# MICROCONTROLLER.net
KiCad netlist of a schematic drawn in Altium Designer
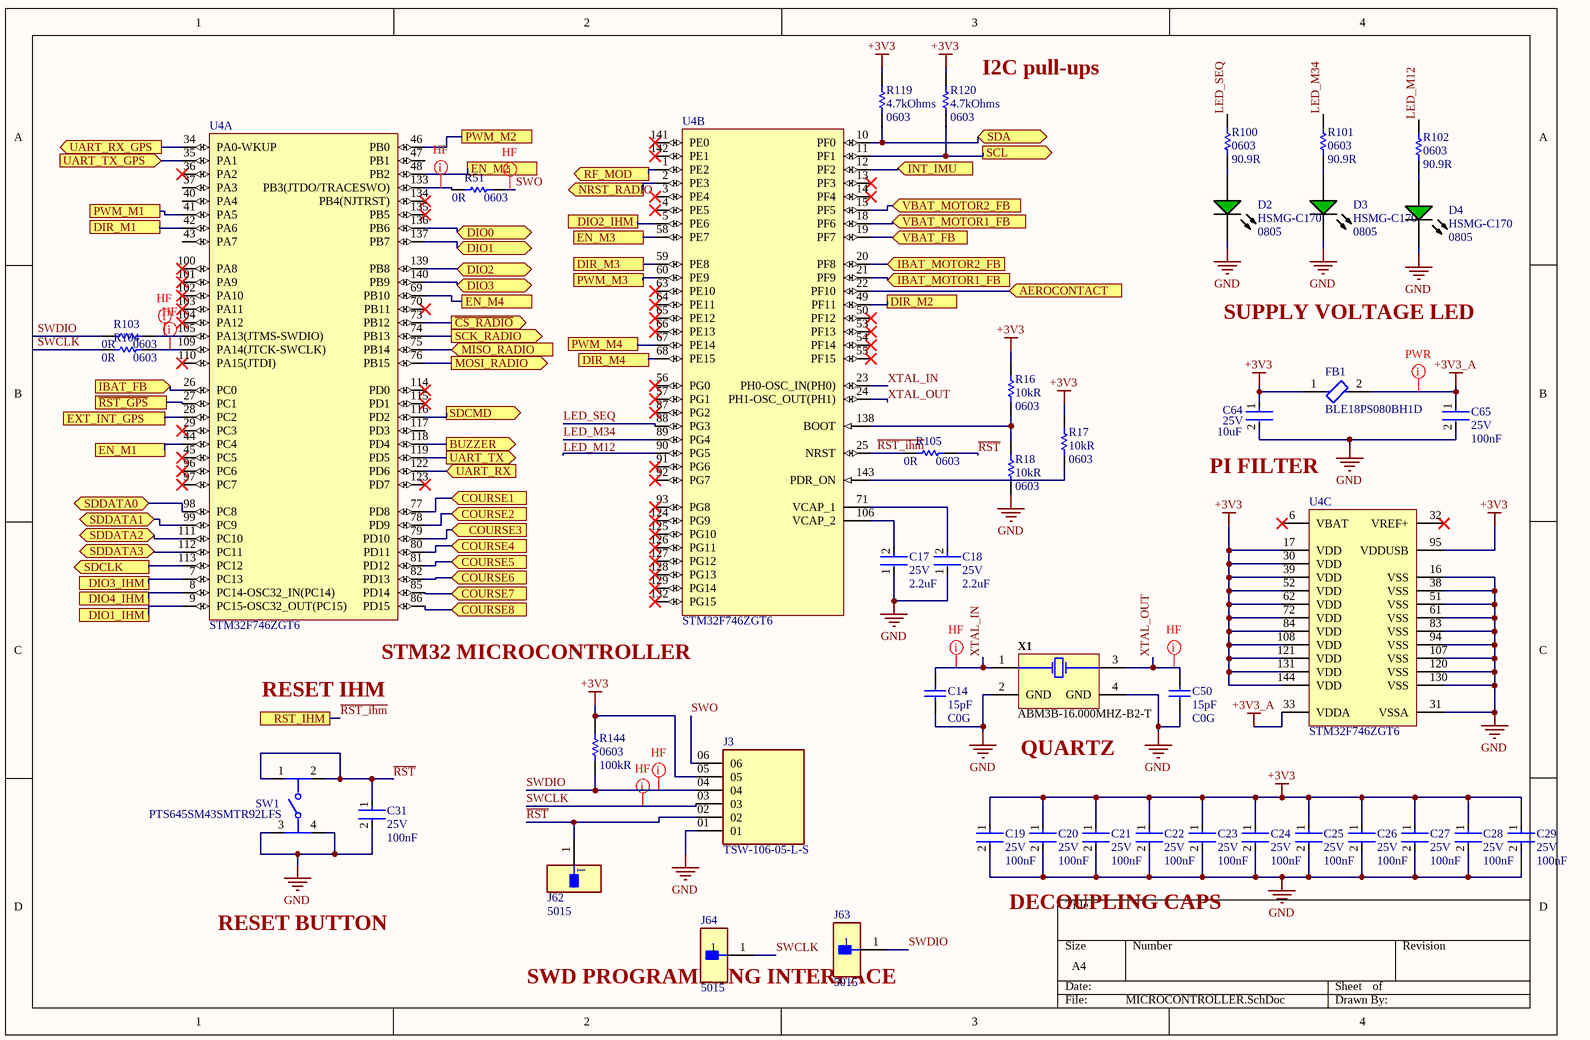
[diagram p0: MICROCONTROLLER.SchDoc]

(export (version "E")
  (design (tool "Eeschema 10.0.6"))
  (components
    (comp (ref "C14")
      (value "VJ0603D150JXPAJ")
      (footprint "CAPC1608X92X38ML15T08")
      (fields
        (field (name "MANUFACTURER") "Vitramon")
        (field (name "TOLERANCE") "5%")
        (field (name "CAPACITANCE") "15pF")
        (field (name "DIELECTRIC") "C0G")
        (field (name "VOLTAGE") "250V")
      )
      (libsource (lib "Altium Content Vault") (part "CAP"))
    )
    (comp (ref "C17")
      (value "C1608X5R1E225K080AB")
      (footprint "FP-C1608-080-0_1-MFG")
      (description "Multilayer Ceramic Capacitors 2.2μF ±10% 25V X5R SMD 0603")
      (fields
        (field (name "VOLTAGE RATING (DC)") "25V")
        (field (name "CAPACITANCE") "2.2uF")
        (field (name "TOLERANCE") "10%")
        (field (name "MANUFACTURER") "TDK")
      )
      (libsource (lib "Altium Content Vault") (part "236180d848d6139a670b325ea6854c9"))
    )
    (comp (ref "C18")
      (value "C1608X5R1E225K080AB")
      (footprint "FP-C1608-080-0_1-MFG")
      (description "Multilayer Ceramic Capacitors 2.2μF ±10% 25V X5R SMD 0603")
      (fields
        (field (name "VOLTAGE RATING (DC)") "25V")
        (field (name "CAPACITANCE") "2.2uF")
        (field (name "TOLERANCE") "10%")
        (field (name "MANUFACTURER") "TDK")
      )
      (libsource (lib "Altium Content Vault") (part "236180d848d6139a670b325ea6854c9"))
    )
    (comp (ref "C19")
      (value "CGA3E2X7R1E104K080AA")
      (footprint "FP-CGA3E-0_3-0_1-MFG")
      (description "Cap Ceramic 100nF 25V X7R 10% Pad SMD 0603 +125°C Automotive T/R")
      (fields
        (field (name "VOLTAGE RATING (DC)") "25V")
        (field (name "CAPACITANCE") "100nF")
        (field (name "TOLERANCE") "10%")
        (field (name "MANUFACTURER") "TDK")
      )
      (libsource (lib "Altium Content Vault") (part "b4654b650e69147ec39a6b967a45e02"))
    )
    (comp (ref "C20")
      (value "CGA3E2X7R1E104K080AA")
      (footprint "FP-CGA3E-0_3-0_1-MFG")
      (description "Cap Ceramic 100nF 25V X7R 10% Pad SMD 0603 +125°C Automotive T/R")
      (fields
        (field (name "VOLTAGE RATING (DC)") "25V")
        (field (name "CAPACITANCE") "100nF")
        (field (name "TOLERANCE") "10%")
        (field (name "MANUFACTURER") "TDK")
      )
      (libsource (lib "Altium Content Vault") (part "b4654b650e69147ec39a6b967a45e02"))
    )
    (comp (ref "C21")
      (value "CGA3E2X7R1E104K080AA")
      (footprint "FP-CGA3E-0_3-0_1-MFG")
      (description "Cap Ceramic 100nF 25V X7R 10% Pad SMD 0603 +125°C Automotive T/R")
      (fields
        (field (name "VOLTAGE RATING (DC)") "25V")
        (field (name "CAPACITANCE") "100nF")
        (field (name "TOLERANCE") "10%")
        (field (name "MANUFACTURER") "TDK")
      )
      (libsource (lib "Altium Content Vault") (part "b4654b650e69147ec39a6b967a45e02"))
    )
    (comp (ref "C22")
      (value "CGA3E2X7R1E104K080AA")
      (footprint "FP-CGA3E-0_3-0_1-MFG")
      (description "Cap Ceramic 100nF 25V X7R 10% Pad SMD 0603 +125°C Automotive T/R")
      (fields
        (field (name "VOLTAGE RATING (DC)") "25V")
        (field (name "CAPACITANCE") "100nF")
        (field (name "TOLERANCE") "10%")
        (field (name "MANUFACTURER") "TDK")
      )
      (libsource (lib "Altium Content Vault") (part "b4654b650e69147ec39a6b967a45e02"))
    )
    (comp (ref "C23")
      (value "CGA3E2X7R1E104K080AA")
      (footprint "FP-CGA3E-0_3-0_1-MFG")
      (description "Cap Ceramic 100nF 25V X7R 10% Pad SMD 0603 +125°C Automotive T/R")
      (fields
        (field (name "VOLTAGE RATING (DC)") "25V")
        (field (name "CAPACITANCE") "100nF")
        (field (name "TOLERANCE") "10%")
        (field (name "MANUFACTURER") "TDK")
      )
      (libsource (lib "Altium Content Vault") (part "b4654b650e69147ec39a6b967a45e02"))
    )
    (comp (ref "C24")
      (value "CGA3E2X7R1E104K080AA")
      (footprint "FP-CGA3E-0_3-0_1-MFG")
      (description "Cap Ceramic 100nF 25V X7R 10% Pad SMD 0603 +125°C Automotive T/R")
      (fields
        (field (name "VOLTAGE RATING (DC)") "25V")
        (field (name "CAPACITANCE") "100nF")
        (field (name "TOLERANCE") "10%")
        (field (name "MANUFACTURER") "TDK")
      )
      (libsource (lib "Altium Content Vault") (part "b4654b650e69147ec39a6b967a45e02"))
    )
    (comp (ref "C25")
      (value "CGA3E2X7R1E104K080AA")
      (footprint "FP-CGA3E-0_3-0_1-MFG")
      (description "Cap Ceramic 100nF 25V X7R 10% Pad SMD 0603 +125°C Automotive T/R")
      (fields
        (field (name "VOLTAGE RATING (DC)") "25V")
        (field (name "CAPACITANCE") "100nF")
        (field (name "TOLERANCE") "10%")
        (field (name "MANUFACTURER") "TDK")
      )
      (libsource (lib "Altium Content Vault") (part "b4654b650e69147ec39a6b967a45e02"))
    )
    (comp (ref "C26")
      (value "CGA3E2X7R1E104K080AA")
      (footprint "FP-CGA3E-0_3-0_1-MFG")
      (description "Cap Ceramic 100nF 25V X7R 10% Pad SMD 0603 +125°C Automotive T/R")
      (fields
        (field (name "VOLTAGE RATING (DC)") "25V")
        (field (name "CAPACITANCE") "100nF")
        (field (name "TOLERANCE") "10%")
        (field (name "MANUFACTURER") "TDK")
      )
      (libsource (lib "Altium Content Vault") (part "b4654b650e69147ec39a6b967a45e02"))
    )
    (comp (ref "C27")
      (value "CGA3E2X7R1E104K080AA")
      (footprint "FP-CGA3E-0_3-0_1-MFG")
      (description "Cap Ceramic 100nF 25V X7R 10% Pad SMD 0603 +125°C Automotive T/R")
      (fields
        (field (name "VOLTAGE RATING (DC)") "25V")
        (field (name "CAPACITANCE") "100nF")
        (field (name "TOLERANCE") "10%")
        (field (name "MANUFACTURER") "TDK")
      )
      (libsource (lib "Altium Content Vault") (part "b4654b650e69147ec39a6b967a45e02"))
    )
    (comp (ref "C28")
      (value "CGA3E2X7R1E104K080AA")
      (footprint "FP-CGA3E-0_3-0_1-MFG")
      (description "Cap Ceramic 100nF 25V X7R 10% Pad SMD 0603 +125°C Automotive T/R")
      (fields
        (field (name "VOLTAGE RATING (DC)") "25V")
        (field (name "CAPACITANCE") "100nF")
        (field (name "TOLERANCE") "10%")
        (field (name "MANUFACTURER") "TDK")
      )
      (libsource (lib "Altium Content Vault") (part "b4654b650e69147ec39a6b967a45e02"))
    )
    (comp (ref "C29")
      (value "CGA3E2X7R1E104K080AA")
      (footprint "FP-CGA3E-0_3-0_1-MFG")
      (description "Cap Ceramic 100nF 25V X7R 10% Pad SMD 0603 +125°C Automotive T/R")
      (fields
        (field (name "VOLTAGE RATING (DC)") "25V")
        (field (name "CAPACITANCE") "100nF")
        (field (name "TOLERANCE") "10%")
        (field (name "MANUFACTURER") "TDK")
      )
      (libsource (lib "Altium Content Vault") (part "b4654b650e69147ec39a6b967a45e02"))
    )
    (comp (ref "C31")
      (value "CGA3E2X7R1E104K080AA")
      (footprint "FP-CGA3E-0_3-0_1-MFG")
      (description "Cap Ceramic 100nF 25V X7R 10% Pad SMD 0603 +125°C Automotive T/R")
      (fields
        (field (name "VOLTAGE RATING (DC)") "25V")
        (field (name "CAPACITANCE") "100nF")
        (field (name "TOLERANCE") "10%")
        (field (name "MANUFACTURER") "TDK")
      )
      (libsource (lib "Altium Content Vault") (part "b4654b650e69147ec39a6b967a45e02"))
    )
    (comp (ref "C50")
      (value "VJ0603D150JXPAJ")
      (footprint "CAPC1608X92X38ML15T08")
      (fields
        (field (name "MANUFACTURER") "Vitramon")
        (field (name "TOLERANCE") "5%")
        (field (name "CAPACITANCE") "15pF")
        (field (name "DIELECTRIC") "C0G")
        (field (name "VOLTAGE") "250V")
      )
      (libsource (lib "Altium Content Vault") (part "CAP"))
    )
    (comp (ref "C64")
      (value "C2012X5R1E106K125AB")
      (footprint "FP-C2012-125-0_2-IPC_B")
      (description "Multilayer Ceramic Capacitors 10μF ±10% 25V X5R SMD 0805")
      (fields
        (field (name "VOLTAGE") "25V")
        (field (name "VOLTAGE RATING (DC)") "25V")
        (field (name "TOLERANCE") "10%")
        (field (name "CAPACITANCE") "10uF")
      )
      (libsource (lib "Altium Content Vault") (part "b4654b650e69147ec39a6b967a45e02"))
    )
    (comp (ref "C65")
      (value "CGA3E2X7R1E104K080AA")
      (footprint "FP-CGA3E-0_3-0_1-MFG")
      (description "Cap Ceramic 100nF 25V X7R 10% Pad SMD 0603 +125°C Automotive T/R")
      (fields
        (field (name "VOLTAGE RATING (DC)") "25V")
        (field (name "CAPACITANCE") "100nF")
        (field (name "TOLERANCE") "10%")
        (field (name "MANUFACTURER") "TDK")
      )
      (libsource (lib "Altium Content Vault") (part "b4654b650e69147ec39a6b967a45e02"))
    )
    (comp (ref "D2")
      (value "HSMG-C170")
      (footprint "AVAG-HSMX-C170_V")
      (description "Chip LED, Green, 2.2 V, -40 to 85 degC, 2-Pin SMD, Pb-Free, Tape and Reel")
      (fields (field (name "MANUFACTURER") "Avago") (field (name "CASE/PACKAGE") "0805"))
      (libsource (lib "Altium Content Vault") (part "LED_GREEN_A1K2-2"))
    )
    (comp (ref "D3")
      (value "HSMG-C170")
      (footprint "AVAG-HSMX-C170_V")
      (description "Chip LED, Green, 2.2 V, -40 to 85 degC, 2-Pin SMD, Pb-Free, Tape and Reel")
      (fields (field (name "MANUFACTURER") "Avago") (field (name "CASE/PACKAGE") "0805"))
      (libsource (lib "Altium Content Vault") (part "LED_GREEN_A1K2-2"))
    )
    (comp (ref "D4")
      (value "HSMG-C170")
      (footprint "AVAG-HSMX-C170_V")
      (description "Chip LED, Green, 2.2 V, -40 to 85 degC, 2-Pin SMD, Pb-Free, Tape and Reel")
      (fields (field (name "MANUFACTURER") "Avago") (field (name "CASE/PACKAGE") "0805"))
      (libsource (lib "Altium Content Vault") (part "LED_GREEN_A1K2-2"))
    )
    (comp (ref "FB1")
      (value "BLE18PS080BH1D")
      (footprint "FP-BLE18-0_15-t0_6-MFG")
      (description "Ferrite Chip Bead 8.5Ω ±25% 5A, DCR 0.004Ω 0603 AEC-200")
      (fields (field (name "MANUFACTURER") "Murata"))
      (libsource (lib "Altium Content Vault") (part "5f30dd21d616792df468990f7003faa"))
    )
    (comp (ref "J3")
      (value "TSW-106-05-L-S")
      (footprint "TSW-106-05-L-S:SAMTEC_TSW-106-05-L-S")
      (fields (field (name "MF") "{'manufacturer': u'Samtec'}"))
      (libsource (lib "*") (part "TSW-106-05-L-S"))
    )
    (comp (ref "J62")
      (value "5015")
      (footprint "FP-5015-MFG")
      (description "PC TEST POINT MINIATURE")
      (fields
        (field (name "MANUFACTURER") "keystone")
        (field (name "OCTOPART") "https://octopart.com/5015-keystone-3822")
      )
      (libsource (lib "Altium Content Vault") (part "dd45045ce8184df9e99e12baf3f412c"))
    )
    (comp (ref "J63")
      (value "5015")
      (footprint "FP-5015-MFG")
      (description "PC TEST POINT MINIATURE")
      (fields
        (field (name "MANUFACTURER") "keystone")
        (field (name "OCTOPART") "https://octopart.com/5015-keystone-3822")
      )
      (libsource (lib "Altium Content Vault") (part "dd45045ce8184df9e99e12baf3f412c"))
    )
    (comp (ref "J64")
      (value "5015")
      (footprint "FP-5015-MFG")
      (description "PC TEST POINT MINIATURE")
      (fields
        (field (name "MANUFACTURER") "keystone")
        (field (name "OCTOPART") "https://octopart.com/5015-keystone-3822")
      )
      (libsource (lib "Altium Content Vault") (part "dd45045ce8184df9e99e12baf3f412c"))
    )
    (comp (ref "R16")
      (value "ERJ3EKF1002V")
      (footprint "RESC1609X55X30LL15T15")
      (description "Chip Resistor, 10 KOhm, +/- 1%, 0.1 W, -55 to 155 degC, 0603 (1608 Metric), RoHS, Tape and Reel")
      (fields
        (field (name "RESISTANCE") "10kR")
        (field (name "CASE CODE (IMPERIAL)") "0603")
        (field (name "TOLERANCE") "1%")
        (field (name "MANUFACTURER") "Panasonic")
      )
      (libsource (lib "Altium Content Vault") (part "RES-2"))
    )
    (comp (ref "R17")
      (value "ERJ3EKF1002V")
      (footprint "RESC1609X55X30LL15T15")
      (description "Chip Resistor, 10 KOhm, +/- 1%, 0.1 W, -55 to 155 degC, 0603 (1608 Metric), RoHS, Tape and Reel")
      (fields
        (field (name "RESISTANCE") "10kR")
        (field (name "CASE CODE (IMPERIAL)") "0603")
        (field (name "TOLERANCE") "1%")
        (field (name "MANUFACTURER") "Panasonic")
      )
      (libsource (lib "Altium Content Vault") (part "RES-2"))
    )
    (comp (ref "R18")
      (value "ERJ3EKF1002V")
      (footprint "RESC1609X55X30LL15T15")
      (description "Chip Resistor, 10 KOhm, +/- 1%, 0.1 W, -55 to 155 degC, 0603 (1608 Metric), RoHS, Tape and Reel")
      (fields
        (field (name "RESISTANCE") "10kR")
        (field (name "CASE CODE (IMPERIAL)") "0603")
        (field (name "TOLERANCE") "1%")
        (field (name "MANUFACTURER") "Panasonic")
      )
      (libsource (lib "Altium Content Vault") (part "RES-2"))
    )
    (comp (ref "R51")
      (value "RC0603JR-070RL")
      (footprint "RESC1608X55X25ML10T15")
      (description "Chip Resistor, 0 Ohm, +/- 5%, 0.1 W, -55 to 155 degC, 0603 (1608 Metric), RoHS, Tape and Reel")
      (fields
        (field (name "TOLERANCE") "5%")
        (field (name "CASE CODE (IMPERIAL)") "0603")
        (field (name "RESISTANCE") "0R")
        (field (name "MANUFACTURER") "Yageo")
      )
      (libsource (lib "Altium Content Vault") (part "RES-2"))
    )
    (comp (ref "R100")
      (value "CRCW060390R9FKEA")
      (footprint "RESC1609X50X30NL10T20")
      (fields
        (field (name "MANUFACTURER") "Vishay Dale")
        (field (name "CASE CODE (IMPERIAL)") "0603")
        (field (name "RESISTANCE") "90.9R")
        (field (name "TOLERANCE") "1%")
      )
      (libsource (lib "Altium Content Vault") (part "RES"))
    )
    (comp (ref "R101")
      (value "CRCW060390R9FKEA")
      (footprint "RESC1609X50X30NL10T20")
      (fields
        (field (name "MANUFACTURER") "Vishay Dale")
        (field (name "CASE CODE (IMPERIAL)") "0603")
        (field (name "RESISTANCE") "90.9R")
        (field (name "TOLERANCE") "1%")
      )
      (libsource (lib "Altium Content Vault") (part "RES"))
    )
    (comp (ref "R102")
      (value "CRCW060390R9FKEA")
      (footprint "RESC1609X50X30NL10T20")
      (fields
        (field (name "MANUFACTURER") "Vishay Dale")
        (field (name "CASE CODE (IMPERIAL)") "0603")
        (field (name "RESISTANCE") "90.9R")
        (field (name "TOLERANCE") "1%")
      )
      (libsource (lib "Altium Content Vault") (part "RES"))
    )
    (comp (ref "R103")
      (value "RC0603JR-070RL")
      (footprint "RESC1608X55X25ML10T15")
      (description "Chip Resistor, 0 Ohm, +/- 5%, 0.1 W, -55 to 155 degC, 0603 (1608 Metric), RoHS, Tape and Reel")
      (fields
        (field (name "TOLERANCE") "5%")
        (field (name "CASE CODE (IMPERIAL)") "0603")
        (field (name "RESISTANCE") "0R")
        (field (name "MANUFACTURER") "Yageo")
      )
      (libsource (lib "Altium Content Vault") (part "RES-2"))
    )
    (comp (ref "R104")
      (value "RC0603JR-070RL")
      (footprint "RESC1608X55X25ML10T15")
      (description "Chip Resistor, 0 Ohm, +/- 5%, 0.1 W, -55 to 155 degC, 0603 (1608 Metric), RoHS, Tape and Reel")
      (fields
        (field (name "TOLERANCE") "5%")
        (field (name "CASE CODE (IMPERIAL)") "0603")
        (field (name "RESISTANCE") "0R")
        (field (name "MANUFACTURER") "Yageo")
      )
      (libsource (lib "Altium Content Vault") (part "RES-2"))
    )
    (comp (ref "R105")
      (value "RC0603JR-070RL")
      (footprint "RESC1608X55X25ML10T15")
      (description "Chip Resistor, 0 Ohm, +/- 5%, 0.1 W, -55 to 155 degC, 0603 (1608 Metric), RoHS, Tape and Reel")
      (fields
        (field (name "TOLERANCE") "5%")
        (field (name "CASE CODE (IMPERIAL)") "0603")
        (field (name "RESISTANCE") "0R")
        (field (name "MANUFACTURER") "Yageo")
      )
      (libsource (lib "Altium Content Vault") (part "RES-2"))
    )
    (comp (ref "R119")
      (value "RC0603FR-074K7L")
      (footprint "RESC1608X55X25LL10T15")
      (description "Chip Resistor, 4.7 KOhm, +/- 1%, 0.1 W, -55 to 155 degC, 0603 (1608 Metric), RoHS, Tape and Reel")
      (fields
        (field (name "MANUFACTURER") "Yageo")
        (field (name "RESISTANCE") "4.7kOhms")
        (field (name "CASE CODE - IN") "0603")
        (field (name "TOLERANCE") "1%")
      )
      (libsource (lib "Altium Content Vault") (part "RES-2"))
    )
    (comp (ref "R120")
      (value "RC0603FR-074K7L")
      (footprint "RESC1608X55X25LL10T15")
      (description "Chip Resistor, 4.7 KOhm, +/- 1%, 0.1 W, -55 to 155 degC, 0603 (1608 Metric), RoHS, Tape and Reel")
      (fields
        (field (name "MANUFACTURER") "Yageo")
        (field (name "RESISTANCE") "4.7kOhms")
        (field (name "CASE CODE - IN") "0603")
        (field (name "TOLERANCE") "1%")
      )
      (libsource (lib "Altium Content Vault") (part "RES-2"))
    )
    (comp (ref "R144")
      (value "ERA3AEB104V")
      (footprint "RESC1608X55X30ML20T20")
      (fields
        (field (name "MANUFACTURER") "Panasonic")
        (field (name "MANUFACTURER PART NUMBER") "ERA-3AEB104V")
        (field (name "CASE CODE (IMPERIAL)") "0603")
        (field (name "RESISTANCE") "100kR")
        (field (name "TOLERANCE") "0.1%")
      )
      (libsource (lib "Altium Content Vault") (part "RES"))
    )
    (comp (ref "SW1")
      (value "PTS645SM43SMTR92LFS")
      (footprint "FP-PTS645SM43SMTR92LFS-MFG")
      (description "SWITCH TACTILE SPST-NO 0.05A 12V")
      (libsource (lib "Altium Content Vault") (part "1adf0dd01260c80cf25a44bfd6b99ba"))
    )
    (comp (ref "U4")
      (value "STM32F746ZGT6")
      (footprint "STM-LQFP144_V")
      (fields (field (name "PARTNUMBER") "STM32F746ZG") (field (name "MANUFACTURER") "STMicroelectronics"))
      (libsource (lib "Altium Content Vault") (part "STM-STM32F74X-LQFP-144"))
    )
    (comp (ref "X1")
      (value "ABM3B-16.000MHZ-B2-T")
      (footprint "ABRA-ABM3B-4_V")
      (description "Ceramic SMD Crystal, 16 MHz, +/- 20 ppm, 50 Ohm, -20 to 70 degC, 4-Pin SMD, RoHS, Tape and Reel")
      (fields (field (name "TOLERANCE") "30%"))
      (libsource (lib "Altium Content Vault") (part "XTAL-1-3-4"))
    )
  )
  (nets
    (net (code "1") (name "+3V3") (class "Default")
      (node (ref "C19") (pin "1") (pinfunction "1_1") (pintype "passive"))
      (node (ref "C20") (pin "1") (pinfunction "1_1") (pintype "passive"))
      (node (ref "C21") (pin "1") (pinfunction "1_1") (pintype "passive"))
      (node (ref "C22") (pin "1") (pinfunction "1_1") (pintype "passive"))
      (node (ref "C23") (pin "1") (pinfunction "1_1") (pintype "passive"))
      (node (ref "C24") (pin "1") (pinfunction "1_1") (pintype "passive"))
      (node (ref "C25") (pin "1") (pinfunction "1_1") (pintype "passive"))
      (node (ref "C26") (pin "1") (pinfunction "1_1") (pintype "passive"))
      (node (ref "C27") (pin "1") (pinfunction "1_1") (pintype "passive"))
      (node (ref "C28") (pin "1") (pinfunction "1_1") (pintype "passive"))
      (node (ref "C29") (pin "1") (pinfunction "1_1") (pintype "passive"))
      (node (ref "C64") (pin "1") (pinfunction "1_1") (pintype "passive"))
      (node (ref "FB1") (pin "1") (pinfunction "1_1") (pintype "passive"))
      (node (ref "J3") (pin "05") (pinfunction "05_05") (pintype "passive"))
      (node (ref "R119") (pin "2") (pinfunction "2_2") (pintype "passive"))
      (node (ref "R120") (pin "2") (pinfunction "2_2") (pintype "passive"))
      (node (ref "R144") (pin "2") (pinfunction "2_2") (pintype "passive"))
      (node (ref "R16") (pin "2") (pinfunction "2_2") (pintype "passive"))
      (node (ref "R17") (pin "2") (pinfunction "2_2") (pintype "passive"))
      (node (ref "U4") (pin "108") (pinfunction "VDD_108") (pintype "power_in"))
      (node (ref "U4") (pin "121") (pinfunction "VDD_121") (pintype "power_in"))
      (node (ref "U4") (pin "131") (pinfunction "VDD_131") (pintype "power_in"))
      (node (ref "U4") (pin "144") (pinfunction "VDD_144") (pintype "power_in"))
      (node (ref "U4") (pin "17") (pinfunction "VDD_17") (pintype "power_in"))
      (node (ref "U4") (pin "30") (pinfunction "VDD_30") (pintype "power_in"))
      (node (ref "U4") (pin "39") (pinfunction "VDD_39") (pintype "power_in"))
      (node (ref "U4") (pin "52") (pinfunction "VDD_52") (pintype "power_in"))
      (node (ref "U4") (pin "62") (pinfunction "VDD_62") (pintype "power_in"))
      (node (ref "U4") (pin "72") (pinfunction "VDD_72") (pintype "power_in"))
      (node (ref "U4") (pin "84") (pinfunction "VDD_84") (pintype "power_in"))
      (node (ref "U4") (pin "95") (pinfunction "VDDUSB_95") (pintype "power_in"))
    )
    (net (code "2") (name "+3V3_A") (class "Default")
      (node (ref "C65") (pin "1") (pinfunction "1_1") (pintype "passive"))
      (node (ref "FB1") (pin "2") (pinfunction "2_2") (pintype "passive"))
      (node (ref "U4") (pin "33") (pinfunction "VDDA_33") (pintype "power_in"))
    )
    (net (code "3") (name "/AEROCONTACT") (class "Default")
      (node (ref "U4") (pin "22") (pinfunction "PF10_22") (pintype "bidirectional"))
    )
    (net (code "4") (name "/BUZZER") (class "Default")
      (node (ref "U4") (pin "118") (pinfunction "PD4_118") (pintype "bidirectional"))
    )
    (net (code "5") (name "/COURSE1") (class "Default")
      (node (ref "U4") (pin "77") (pinfunction "PD8_77") (pintype "bidirectional"))
    )
    (net (code "6") (name "/COURSE2") (class "Default")
      (node (ref "U4") (pin "78") (pinfunction "PD9_78") (pintype "bidirectional"))
    )
    (net (code "7") (name "/COURSE3") (class "Default")
      (node (ref "U4") (pin "79") (pinfunction "PD10_79") (pintype "bidirectional"))
    )
    (net (code "8") (name "/COURSE4") (class "Default")
      (node (ref "U4") (pin "80") (pinfunction "PD11_80") (pintype "bidirectional"))
    )
    (net (code "9") (name "/COURSE5") (class "Default")
      (node (ref "U4") (pin "81") (pinfunction "PD12_81") (pintype "bidirectional"))
    )
    (net (code "10") (name "/COURSE6") (class "Default")
      (node (ref "U4") (pin "82") (pinfunction "PD13_82") (pintype "bidirectional"))
    )
    (net (code "11") (name "/COURSE7") (class "Default")
      (node (ref "U4") (pin "85") (pinfunction "PD14_85") (pintype "bidirectional"))
    )
    (net (code "12") (name "/COURSE8") (class "Default")
      (node (ref "U4") (pin "86") (pinfunction "PD15_86") (pintype "bidirectional"))
    )
    (net (code "13") (name "/CS_RADIO") (class "Default")
      (node (ref "U4") (pin "73") (pinfunction "PB12_73") (pintype "bidirectional"))
    )
    (net (code "14") (name "/DIO0") (class "Default")
      (node (ref "U4") (pin "136") (pinfunction "PB6_136") (pintype "bidirectional"))
    )
    (net (code "15") (name "/DIO1") (class "Default")
      (node (ref "U4") (pin "137") (pinfunction "PB7_137") (pintype "bidirectional"))
    )
    (net (code "16") (name "/DIO1_IHM") (class "Default")
      (node (ref "U4") (pin "9") (pinfunction "PC15-OSC32_OUT(PC15)_9") (pintype "bidirectional"))
    )
    (net (code "17") (name "/DIO2") (class "Default")
      (node (ref "U4") (pin "139") (pinfunction "PB8_139") (pintype "bidirectional"))
    )
    (net (code "18") (name "/DIO2_IHM") (class "Default")
      (node (ref "U4") (pin "5") (pinfunction "PE6_5") (pintype "bidirectional"))
    )
    (net (code "19") (name "/DIO3") (class "Default")
      (node (ref "U4") (pin "140") (pinfunction "PB9_140") (pintype "bidirectional"))
    )
    (net (code "20") (name "/DIO3_IHM") (class "Default")
      (node (ref "U4") (pin "7") (pinfunction "PC13_7") (pintype "bidirectional"))
    )
    (net (code "21") (name "/DIO4_IHM") (class "Default")
      (node (ref "U4") (pin "8") (pinfunction "PC14-OSC32_IN(PC14)_8") (pintype "bidirectional"))
    )
    (net (code "22") (name "/DIR_M1") (class "Default")
      (node (ref "U4") (pin "42") (pinfunction "PA6_42") (pintype "bidirectional"))
    )
    (net (code "23") (name "/DIR_M2") (class "Default")
      (node (ref "U4") (pin "49") (pinfunction "PF11_49") (pintype "bidirectional"))
    )
    (net (code "24") (name "/DIR_M3") (class "Default")
      (node (ref "U4") (pin "59") (pinfunction "PE8_59") (pintype "bidirectional"))
    )
    (net (code "25") (name "/DIR_M4") (class "Default")
      (node (ref "U4") (pin "68") (pinfunction "PE15_68") (pintype "bidirectional"))
    )
    (net (code "26") (name "/EN_M1") (class "Default")
      (node (ref "U4") (pin "44") (pinfunction "PC4_44") (pintype "bidirectional"))
    )
    (net (code "27") (name "/EN_M2") (class "Default")
      (node (ref "U4") (pin "48") (pinfunction "PB2_48") (pintype "bidirectional"))
    )
    (net (code "28") (name "/EN_M3") (class "Default")
      (node (ref "U4") (pin "58") (pinfunction "PE7_58") (pintype "bidirectional"))
    )
    (net (code "29") (name "/EN_M4") (class "Default")
      (node (ref "U4") (pin "69") (pinfunction "PB10_69") (pintype "bidirectional"))
    )
    (net (code "30") (name "/EXT_INT_GPS") (class "Default")
      (node (ref "U4") (pin "28") (pinfunction "PC2_28") (pintype "bidirectional"))
    )
    (net (code "31") (name "/IBAT_FB") (class "Default")
      (node (ref "U4") (pin "26") (pinfunction "PC0_26") (pintype "bidirectional"))
    )
    (net (code "32") (name "/IBAT_MOTOR1_FB") (class "Default")
      (node (ref "U4") (pin "21") (pinfunction "PF9_21") (pintype "bidirectional"))
    )
    (net (code "33") (name "/IBAT_MOTOR2_FB") (class "Default")
      (node (ref "U4") (pin "20") (pinfunction "PF8_20") (pintype "bidirectional"))
    )
    (net (code "34") (name "/INT_IMU") (class "Default")
      (node (ref "U4") (pin "12") (pinfunction "PF2_12") (pintype "bidirectional"))
    )
    (net (code "35") (name "/LED_M12") (class "Default")
      (node (ref "R102") (pin "2") (pinfunction "2_2") (pintype "passive"))
      (node (ref "U4") (pin "90") (pinfunction "PG5_90") (pintype "bidirectional"))
    )
    (net (code "36") (name "/LED_M34") (class "Default")
      (node (ref "R101") (pin "2") (pinfunction "2_2") (pintype "passive"))
      (node (ref "U4") (pin "89") (pinfunction "PG4_89") (pintype "bidirectional"))
    )
    (net (code "37") (name "/LED_SEQ") (class "Default")
      (node (ref "R100") (pin "2") (pinfunction "2_2") (pintype "passive"))
      (node (ref "U4") (pin "88") (pinfunction "PG3_88") (pintype "bidirectional"))
    )
    (net (code "38") (name "/MISO_RADIO") (class "Default")
      (node (ref "U4") (pin "75") (pinfunction "PB14_75") (pintype "bidirectional"))
    )
    (net (code "39") (name "/MOSI_RADIO") (class "Default")
      (node (ref "U4") (pin "76") (pinfunction "PB15_76") (pintype "bidirectional"))
    )
    (net (code "40") (name "/NRST_RADIO") (class "Default")
      (node (ref "U4") (pin "2") (pinfunction "PE3_2") (pintype "bidirectional"))
    )
    (net (code "41") (name "/PWM_M1") (class "Default")
      (node (ref "U4") (pin "41") (pinfunction "PA5_41") (pintype "bidirectional"))
    )
    (net (code "42") (name "/PWM_M2") (class "Default")
      (node (ref "U4") (pin "46") (pinfunction "PB0_46") (pintype "bidirectional"))
    )
    (net (code "43") (name "/PWM_M3") (class "Default")
      (node (ref "U4") (pin "60") (pinfunction "PE9_60") (pintype "bidirectional"))
    )
    (net (code "44") (name "/PWM_M4") (class "Default")
      (node (ref "U4") (pin "67") (pinfunction "PE14_67") (pintype "bidirectional"))
    )
    (net (code "45") (name "/RF_MOD") (class "Default")
      (node (ref "U4") (pin "1") (pinfunction "PE2_1") (pintype "bidirectional"))
    )
    (net (code "46") (name "/RST") (class "Default")
      (node (ref "C31") (pin "1") (pinfunction "1_1") (pintype "passive"))
      (node (ref "J3") (pin "02") (pinfunction "02_02") (pintype "passive"))
      (node (ref "J62") (pin "1") (pinfunction "1_1") (pintype "passive"))
      (node (ref "R105") (pin "2") (pinfunction "2_2") (pintype "passive"))
      (node (ref "SW1") (pin "1") (pinfunction "1_1") (pintype "passive"))
      (node (ref "SW1") (pin "2") (pinfunction "2_2") (pintype "passive"))
    )
    (net (code "47") (name "/RST_GPS") (class "Default")
      (node (ref "U4") (pin "27") (pinfunction "PC1_27") (pintype "bidirectional"))
    )
    (net (code "48") (name "/RST_ihm") (class "Default")
      (node (ref "R105") (pin "1") (pinfunction "1_1") (pintype "passive"))
      (node (ref "U4") (pin "25") (pinfunction "NRST_25") (pintype "bidirectional"))
    )
    (net (code "49") (name "/SCK_RADIO") (class "Default")
      (node (ref "U4") (pin "74") (pinfunction "PB13_74") (pintype "bidirectional"))
    )
    (net (code "50") (name "/SCL") (class "Default")
      (node (ref "R120") (pin "1") (pinfunction "1_1") (pintype "passive"))
      (node (ref "U4") (pin "11") (pinfunction "PF1_11") (pintype "bidirectional"))
    )
    (net (code "51") (name "/SDA") (class "Default")
      (node (ref "R119") (pin "1") (pinfunction "1_1") (pintype "passive"))
      (node (ref "U4") (pin "10") (pinfunction "PF0_10") (pintype "bidirectional"))
    )
    (net (code "52") (name "/SDCLK") (class "Default")
      (node (ref "U4") (pin "113") (pinfunction "PC12_113") (pintype "bidirectional"))
    )
    (net (code "53") (name "/SDCMD") (class "Default")
      (node (ref "U4") (pin "116") (pinfunction "PD2_116") (pintype "bidirectional"))
    )
    (net (code "54") (name "/SDDATA0") (class "Default")
      (node (ref "U4") (pin "98") (pinfunction "PC8_98") (pintype "bidirectional"))
    )
    (net (code "55") (name "/SDDATA1") (class "Default")
      (node (ref "U4") (pin "99") (pinfunction "PC9_99") (pintype "bidirectional"))
    )
    (net (code "56") (name "/SDDATA2") (class "Default")
      (node (ref "U4") (pin "111") (pinfunction "PC10_111") (pintype "bidirectional"))
    )
    (net (code "57") (name "/SDDATA3") (class "Default")
      (node (ref "U4") (pin "112") (pinfunction "PC11_112") (pintype "bidirectional"))
    )
    (net (code "58") (name "/SWCLK") (class "Default")
      (node (ref "J3") (pin "03") (pinfunction "03_03") (pintype "passive"))
      (node (ref "J64") (pin "1") (pinfunction "1_1") (pintype "passive"))
      (node (ref "R104") (pin "1") (pinfunction "1_1") (pintype "passive"))
    )
    (net (code "59") (name "/SWDIO") (class "Default")
      (node (ref "J3") (pin "04") (pinfunction "04_04") (pintype "passive"))
      (node (ref "J63") (pin "1") (pinfunction "1_1") (pintype "passive"))
      (node (ref "R103") (pin "1") (pinfunction "1_1") (pintype "passive"))
      (node (ref "R144") (pin "1") (pinfunction "1_1") (pintype "passive"))
    )
    (net (code "60") (name "/SWO") (class "Default")
      (node (ref "J3") (pin "06") (pinfunction "06_06") (pintype "passive"))
      (node (ref "R51") (pin "2") (pinfunction "2_2") (pintype "passive"))
    )
    (net (code "61") (name "/UART_RX") (class "Default")
      (node (ref "U4") (pin "122") (pinfunction "PD6_122") (pintype "bidirectional"))
    )
    (net (code "62") (name "/UART_RX_GPS") (class "Default")
      (node (ref "U4") (pin "34") (pinfunction "PA0-WKUP_34") (pintype "bidirectional"))
    )
    (net (code "63") (name "/UART_TX") (class "Default")
      (node (ref "U4") (pin "119") (pinfunction "PD5_119") (pintype "bidirectional"))
    )
    (net (code "64") (name "/UART_TX_GPS") (class "Default")
      (node (ref "U4") (pin "35") (pinfunction "PA1_35") (pintype "bidirectional"))
    )
    (net (code "65") (name "/VBAT_FB") (class "Default")
      (node (ref "U4") (pin "19") (pinfunction "PF7_19") (pintype "bidirectional"))
    )
    (net (code "66") (name "/VBAT_MOTOR1_FB") (class "Default")
      (node (ref "U4") (pin "18") (pinfunction "PF6_18") (pintype "bidirectional"))
    )
    (net (code "67") (name "/VBAT_MOTOR2_FB") (class "Default")
      (node (ref "U4") (pin "15") (pinfunction "PF5_15") (pintype "bidirectional"))
    )
    (net (code "68") (name "/XTAL_IN") (class "Default")
      (node (ref "C14") (pin "2") (pinfunction "2_2") (pintype "passive"))
      (node (ref "U4") (pin "23") (pinfunction "PH0-OSC_IN(PH0)_23") (pintype "bidirectional"))
      (node (ref "X1") (pin "1") (pinfunction "X1_1") (pintype "passive"))
    )
    (net (code "69") (name "/XTAL_OUT") (class "Default")
      (node (ref "C50") (pin "2") (pinfunction "2_2") (pintype "passive"))
      (node (ref "U4") (pin "24") (pinfunction "PH1-OSC_OUT(PH1)_24") (pintype "bidirectional"))
      (node (ref "X1") (pin "3") (pinfunction "X2_3") (pintype "passive"))
    )
    (net (code "70") (name "GND") (class "Default")
      (node (ref "C14") (pin "1") (pinfunction "1_1") (pintype "passive"))
      (node (ref "C17") (pin "1") (pinfunction "1_1") (pintype "passive"))
      (node (ref "C18") (pin "1") (pinfunction "1_1") (pintype "passive"))
      (node (ref "C19") (pin "2") (pinfunction "2_2") (pintype "passive"))
      (node (ref "C20") (pin "2") (pinfunction "2_2") (pintype "passive"))
      (node (ref "C21") (pin "2") (pinfunction "2_2") (pintype "passive"))
      (node (ref "C22") (pin "2") (pinfunction "2_2") (pintype "passive"))
      (node (ref "C23") (pin "2") (pinfunction "2_2") (pintype "passive"))
      (node (ref "C24") (pin "2") (pinfunction "2_2") (pintype "passive"))
      (node (ref "C25") (pin "2") (pinfunction "2_2") (pintype "passive"))
      (node (ref "C26") (pin "2") (pinfunction "2_2") (pintype "passive"))
      (node (ref "C27") (pin "2") (pinfunction "2_2") (pintype "passive"))
      (node (ref "C28") (pin "2") (pinfunction "2_2") (pintype "passive"))
      (node (ref "C29") (pin "2") (pinfunction "2_2") (pintype "passive"))
      (node (ref "C31") (pin "2") (pinfunction "2_2") (pintype "passive"))
      (node (ref "C50") (pin "1") (pinfunction "1_1") (pintype "passive"))
      (node (ref "C64") (pin "2") (pinfunction "2_2") (pintype "passive"))
      (node (ref "C65") (pin "2") (pinfunction "2_2") (pintype "passive"))
      (node (ref "D2") (pin "2") (pinfunction "K_2") (pintype "passive"))
      (node (ref "D3") (pin "2") (pinfunction "K_2") (pintype "passive"))
      (node (ref "D4") (pin "2") (pinfunction "K_2") (pintype "passive"))
      (node (ref "J3") (pin "01") (pinfunction "01_01") (pintype "passive"))
      (node (ref "R18") (pin "1") (pinfunction "1_1") (pintype "passive"))
      (node (ref "SW1") (pin "3") (pinfunction "3_3") (pintype "passive"))
      (node (ref "SW1") (pin "4") (pinfunction "4_4") (pintype "passive"))
      (node (ref "U4") (pin "107") (pinfunction "VSS_107") (pintype "power_in"))
      (node (ref "U4") (pin "120") (pinfunction "VSS_120") (pintype "power_in"))
      (node (ref "U4") (pin "130") (pinfunction "VSS_130") (pintype "power_in"))
      (node (ref "U4") (pin "16") (pinfunction "VSS_16") (pintype "power_in"))
      (node (ref "U4") (pin "31") (pinfunction "VSSA_31") (pintype "power_in"))
      (node (ref "U4") (pin "38") (pinfunction "VSS_38") (pintype "power_in"))
      (node (ref "U4") (pin "51") (pinfunction "VSS_51") (pintype "power_in"))
      (node (ref "U4") (pin "61") (pinfunction "VSS_61") (pintype "power_in"))
      (node (ref "U4") (pin "83") (pinfunction "VSS_83") (pintype "power_in"))
      (node (ref "U4") (pin "94") (pinfunction "VSS_94") (pintype "power_in"))
      (node (ref "X1") (pin "2") (pinfunction "GND_2") (pintype "power_in"))
      (node (ref "X1") (pin "4") (pinfunction "GND_4") (pintype "power_in"))
    )
    (net (code "71") (name "Net-(D2-A)") (class "Default")
      (node (ref "D2") (pin "1") (pinfunction "A_1") (pintype "passive"))
      (node (ref "R100") (pin "1") (pinfunction "1_1") (pintype "passive"))
    )
    (net (code "72") (name "Net-(D3-A)") (class "Default")
      (node (ref "D3") (pin "1") (pinfunction "A_1") (pintype "passive"))
      (node (ref "R101") (pin "1") (pinfunction "1_1") (pintype "passive"))
    )
    (net (code "73") (name "Net-(D4-A)") (class "Default")
      (node (ref "D4") (pin "1") (pinfunction "A_1") (pintype "passive"))
      (node (ref "R102") (pin "1") (pinfunction "1_1") (pintype "passive"))
    )
    (net (code "74") (name "Net-(U4A-PA13(JTMS-SWDIO))") (class "Default")
      (node (ref "R103") (pin "2") (pinfunction "2_2") (pintype "passive"))
      (node (ref "U4") (pin "105") (pinfunction "PA13(JTMS-SWDIO)_105") (pintype "bidirectional"))
    )
    (net (code "75") (name "Net-(U4A-PA14(JTCK-SWCLK))") (class "Default")
      (node (ref "R104") (pin "2") (pinfunction "2_2") (pintype "passive"))
      (node (ref "U4") (pin "109") (pinfunction "PA14(JTCK-SWCLK)_109") (pintype "bidirectional"))
    )
    (net (code "76") (name "Net-(U4A-PB3(JTDO{slash}TRACESWO))") (class "Default")
      (node (ref "R51") (pin "1") (pinfunction "1_1") (pintype "passive"))
      (node (ref "U4") (pin "133") (pinfunction "PB3(JTDO/TRACESWO)_133") (pintype "bidirectional"))
    )
    (net (code "77") (name "Net-(U4B-BOOT)") (class "Default")
      (node (ref "R16") (pin "1") (pinfunction "1_1") (pintype "passive"))
      (node (ref "R18") (pin "2") (pinfunction "2_2") (pintype "passive"))
      (node (ref "U4") (pin "138") (pinfunction "BOOT_138") (pintype "input"))
    )
    (net (code "78") (name "Net-(U4B-PDR_ON)") (class "Default")
      (node (ref "R17") (pin "1") (pinfunction "1_1") (pintype "passive"))
      (node (ref "U4") (pin "143") (pinfunction "PDR_ON_143") (pintype "input"))
    )
    (net (code "79") (name "Net-(U4B-VCAP_1)") (class "Default")
      (node (ref "C18") (pin "2") (pinfunction "2_2") (pintype "passive"))
      (node (ref "U4") (pin "71") (pinfunction "VCAP_1_71") (pintype "power_in"))
    )
    (net (code "80") (name "Net-(U4B-VCAP_2)") (class "Default")
      (node (ref "C17") (pin "2") (pinfunction "2_2") (pintype "passive"))
      (node (ref "U4") (pin "106") (pinfunction "VCAP_2_106") (pintype "power_in"))
    )
    (net (code "81") (name "unconnected-(U4A-PA2-Pad36)") (class "Default")
      (node (ref "U4") (pin "36") (pinfunction "PA2_36") (pintype "bidirectional+no_connect"))
    )
    (net (code "82") (name "unconnected-(U4A-PA3-Pad37)") (class "Default")
      (node (ref "U4") (pin "37") (pinfunction "PA3_37") (pintype "bidirectional"))
    )
    (net (code "83") (name "unconnected-(U4A-PA4-Pad40)") (class "Default")
      (node (ref "U4") (pin "40") (pinfunction "PA4_40") (pintype "bidirectional"))
    )
    (net (code "84") (name "unconnected-(U4A-PA7-Pad43)") (class "Default")
      (node (ref "U4") (pin "43") (pinfunction "PA7_43") (pintype "bidirectional"))
    )
    (net (code "85") (name "unconnected-(U4A-PA8-Pad100)") (class "Default")
      (node (ref "U4") (pin "100") (pinfunction "PA8_100") (pintype "bidirectional+no_connect"))
    )
    (net (code "86") (name "unconnected-(U4A-PA9-Pad101)") (class "Default")
      (node (ref "U4") (pin "101") (pinfunction "PA9_101") (pintype "bidirectional+no_connect"))
    )
    (net (code "87") (name "unconnected-(U4A-PA10-Pad102)") (class "Default")
      (node (ref "U4") (pin "102") (pinfunction "PA10_102") (pintype "bidirectional+no_connect"))
    )
    (net (code "88") (name "unconnected-(U4A-PA11-Pad103)") (class "Default")
      (node (ref "U4") (pin "103") (pinfunction "PA11_103") (pintype "bidirectional+no_connect"))
    )
    (net (code "89") (name "unconnected-(U4A-PA12-Pad104)") (class "Default")
      (node (ref "U4") (pin "104") (pinfunction "PA12_104") (pintype "bidirectional+no_connect"))
    )
    (net (code "90") (name "unconnected-(U4A-PA15(JTDI)-Pad110)") (class "Default")
      (node (ref "U4") (pin "110") (pinfunction "PA15(JTDI)_110") (pintype "bidirectional+no_connect"))
    )
    (net (code "91") (name "unconnected-(U4A-PB1-Pad47)") (class "Default")
      (node (ref "U4") (pin "47") (pinfunction "PB1_47") (pintype "bidirectional"))
    )
    (net (code "92") (name "unconnected-(U4A-PB4(NJTRST)-Pad134)") (class "Default")
      (node (ref "U4") (pin "134") (pinfunction "PB4(NJTRST)_134") (pintype "bidirectional+no_connect"))
    )
    (net (code "93") (name "unconnected-(U4A-PB5-Pad135)") (class "Default")
      (node (ref "U4") (pin "135") (pinfunction "PB5_135") (pintype "bidirectional+no_connect"))
    )
    (net (code "94") (name "unconnected-(U4A-PB11-Pad70)") (class "Default")
      (node (ref "U4") (pin "70") (pinfunction "PB11_70") (pintype "bidirectional+no_connect"))
    )
    (net (code "95") (name "unconnected-(U4A-PC3-Pad29)") (class "Default")
      (node (ref "U4") (pin "29") (pinfunction "PC3_29") (pintype "bidirectional+no_connect"))
    )
    (net (code "96") (name "unconnected-(U4A-PC5-Pad45)") (class "Default")
      (node (ref "U4") (pin "45") (pinfunction "PC5_45") (pintype "bidirectional+no_connect"))
    )
    (net (code "97") (name "unconnected-(U4A-PC6-Pad96)") (class "Default")
      (node (ref "U4") (pin "96") (pinfunction "PC6_96") (pintype "bidirectional+no_connect"))
    )
    (net (code "98") (name "unconnected-(U4A-PC7-Pad97)") (class "Default")
      (node (ref "U4") (pin "97") (pinfunction "PC7_97") (pintype "bidirectional+no_connect"))
    )
    (net (code "99") (name "unconnected-(U4A-PD0-Pad114)") (class "Default")
      (node (ref "U4") (pin "114") (pinfunction "PD0_114") (pintype "bidirectional+no_connect"))
    )
    (net (code "100") (name "unconnected-(U4A-PD1-Pad115)") (class "Default")
      (node (ref "U4") (pin "115") (pinfunction "PD1_115") (pintype "bidirectional+no_connect"))
    )
    (net (code "101") (name "unconnected-(U4A-PD3-Pad117)") (class "Default")
      (node (ref "U4") (pin "117") (pinfunction "PD3_117") (pintype "bidirectional"))
    )
    (net (code "102") (name "unconnected-(U4A-PD7-Pad123)") (class "Default")
      (node (ref "U4") (pin "123") (pinfunction "PD7_123") (pintype "bidirectional+no_connect"))
    )
    (net (code "103") (name "unconnected-(U4B-PE0-Pad141)") (class "Default")
      (node (ref "U4") (pin "141") (pinfunction "PE0_141") (pintype "bidirectional+no_connect"))
    )
    (net (code "104") (name "unconnected-(U4B-PE1-Pad142)") (class "Default")
      (node (ref "U4") (pin "142") (pinfunction "PE1_142") (pintype "bidirectional+no_connect"))
    )
    (net (code "105") (name "unconnected-(U4B-PE4-Pad3)") (class "Default")
      (node (ref "U4") (pin "3") (pinfunction "PE4_3") (pintype "bidirectional+no_connect"))
    )
    (net (code "106") (name "unconnected-(U4B-PE5-Pad4)") (class "Default")
      (node (ref "U4") (pin "4") (pinfunction "PE5_4") (pintype "bidirectional+no_connect"))
    )
    (net (code "107") (name "unconnected-(U4B-PE10-Pad63)") (class "Default")
      (node (ref "U4") (pin "63") (pinfunction "PE10_63") (pintype "bidirectional+no_connect"))
    )
    (net (code "108") (name "unconnected-(U4B-PE11-Pad64)") (class "Default")
      (node (ref "U4") (pin "64") (pinfunction "PE11_64") (pintype "bidirectional+no_connect"))
    )
    (net (code "109") (name "unconnected-(U4B-PE12-Pad65)") (class "Default")
      (node (ref "U4") (pin "65") (pinfunction "PE12_65") (pintype "bidirectional+no_connect"))
    )
    (net (code "110") (name "unconnected-(U4B-PE13-Pad66)") (class "Default")
      (node (ref "U4") (pin "66") (pinfunction "PE13_66") (pintype "bidirectional+no_connect"))
    )
    (net (code "111") (name "unconnected-(U4B-PF3-Pad13)") (class "Default")
      (node (ref "U4") (pin "13") (pinfunction "PF3_13") (pintype "bidirectional+no_connect"))
    )
    (net (code "112") (name "unconnected-(U4B-PF4-Pad14)") (class "Default")
      (node (ref "U4") (pin "14") (pinfunction "PF4_14") (pintype "bidirectional+no_connect"))
    )
    (net (code "113") (name "unconnected-(U4B-PF12-Pad50)") (class "Default")
      (node (ref "U4") (pin "50") (pinfunction "PF12_50") (pintype "bidirectional+no_connect"))
    )
    (net (code "114") (name "unconnected-(U4B-PF13-Pad53)") (class "Default")
      (node (ref "U4") (pin "53") (pinfunction "PF13_53") (pintype "bidirectional+no_connect"))
    )
    (net (code "115") (name "unconnected-(U4B-PF14-Pad54)") (class "Default")
      (node (ref "U4") (pin "54") (pinfunction "PF14_54") (pintype "bidirectional+no_connect"))
    )
    (net (code "116") (name "unconnected-(U4B-PF15-Pad55)") (class "Default")
      (node (ref "U4") (pin "55") (pinfunction "PF15_55") (pintype "bidirectional+no_connect"))
    )
    (net (code "117") (name "unconnected-(U4B-PG0-Pad56)") (class "Default")
      (node (ref "U4") (pin "56") (pinfunction "PG0_56") (pintype "bidirectional+no_connect"))
    )
    (net (code "118") (name "unconnected-(U4B-PG1-Pad57)") (class "Default")
      (node (ref "U4") (pin "57") (pinfunction "PG1_57") (pintype "bidirectional+no_connect"))
    )
    (net (code "119") (name "unconnected-(U4B-PG2-Pad87)") (class "Default")
      (node (ref "U4") (pin "87") (pinfunction "PG2_87") (pintype "bidirectional+no_connect"))
    )
    (net (code "120") (name "unconnected-(U4B-PG6-Pad91)") (class "Default")
      (node (ref "U4") (pin "91") (pinfunction "PG6_91") (pintype "bidirectional+no_connect"))
    )
    (net (code "121") (name "unconnected-(U4B-PG7-Pad92)") (class "Default")
      (node (ref "U4") (pin "92") (pinfunction "PG7_92") (pintype "bidirectional+no_connect"))
    )
    (net (code "122") (name "unconnected-(U4B-PG8-Pad93)") (class "Default")
      (node (ref "U4") (pin "93") (pinfunction "PG8_93") (pintype "bidirectional+no_connect"))
    )
    (net (code "123") (name "unconnected-(U4B-PG9-Pad124)") (class "Default")
      (node (ref "U4") (pin "124") (pinfunction "PG9_124") (pintype "bidirectional+no_connect"))
    )
    (net (code "124") (name "unconnected-(U4B-PG10-Pad125)") (class "Default")
      (node (ref "U4") (pin "125") (pinfunction "PG10_125") (pintype "bidirectional+no_connect"))
    )
    (net (code "125") (name "unconnected-(U4B-PG11-Pad126)") (class "Default")
      (node (ref "U4") (pin "126") (pinfunction "PG11_126") (pintype "bidirectional+no_connect"))
    )
    (net (code "126") (name "unconnected-(U4B-PG12-Pad127)") (class "Default")
      (node (ref "U4") (pin "127") (pinfunction "PG12_127") (pintype "bidirectional+no_connect"))
    )
    (net (code "127") (name "unconnected-(U4B-PG13-Pad128)") (class "Default")
      (node (ref "U4") (pin "128") (pinfunction "PG13_128") (pintype "bidirectional+no_connect"))
    )
    (net (code "128") (name "unconnected-(U4B-PG14-Pad129)") (class "Default")
      (node (ref "U4") (pin "129") (pinfunction "PG14_129") (pintype "bidirectional+no_connect"))
    )
    (net (code "129") (name "unconnected-(U4B-PG15-Pad132)") (class "Default")
      (node (ref "U4") (pin "132") (pinfunction "PG15_132") (pintype "bidirectional+no_connect"))
    )
    (net (code "130") (name "unconnected-(U4C-VBAT-Pad6)") (class "Default")
      (node (ref "U4") (pin "6") (pinfunction "VBAT_6") (pintype "power_in+no_connect"))
    )
    (net (code "131") (name "unconnected-(U4C-VREF+-Pad32)") (class "Default")
      (node (ref "U4") (pin "32") (pinfunction "VREF+_32") (pintype "power_in+no_connect"))
    )
  )
)
